# theremin.net
KiCad netlist of a schematic drawn in Altium Designer
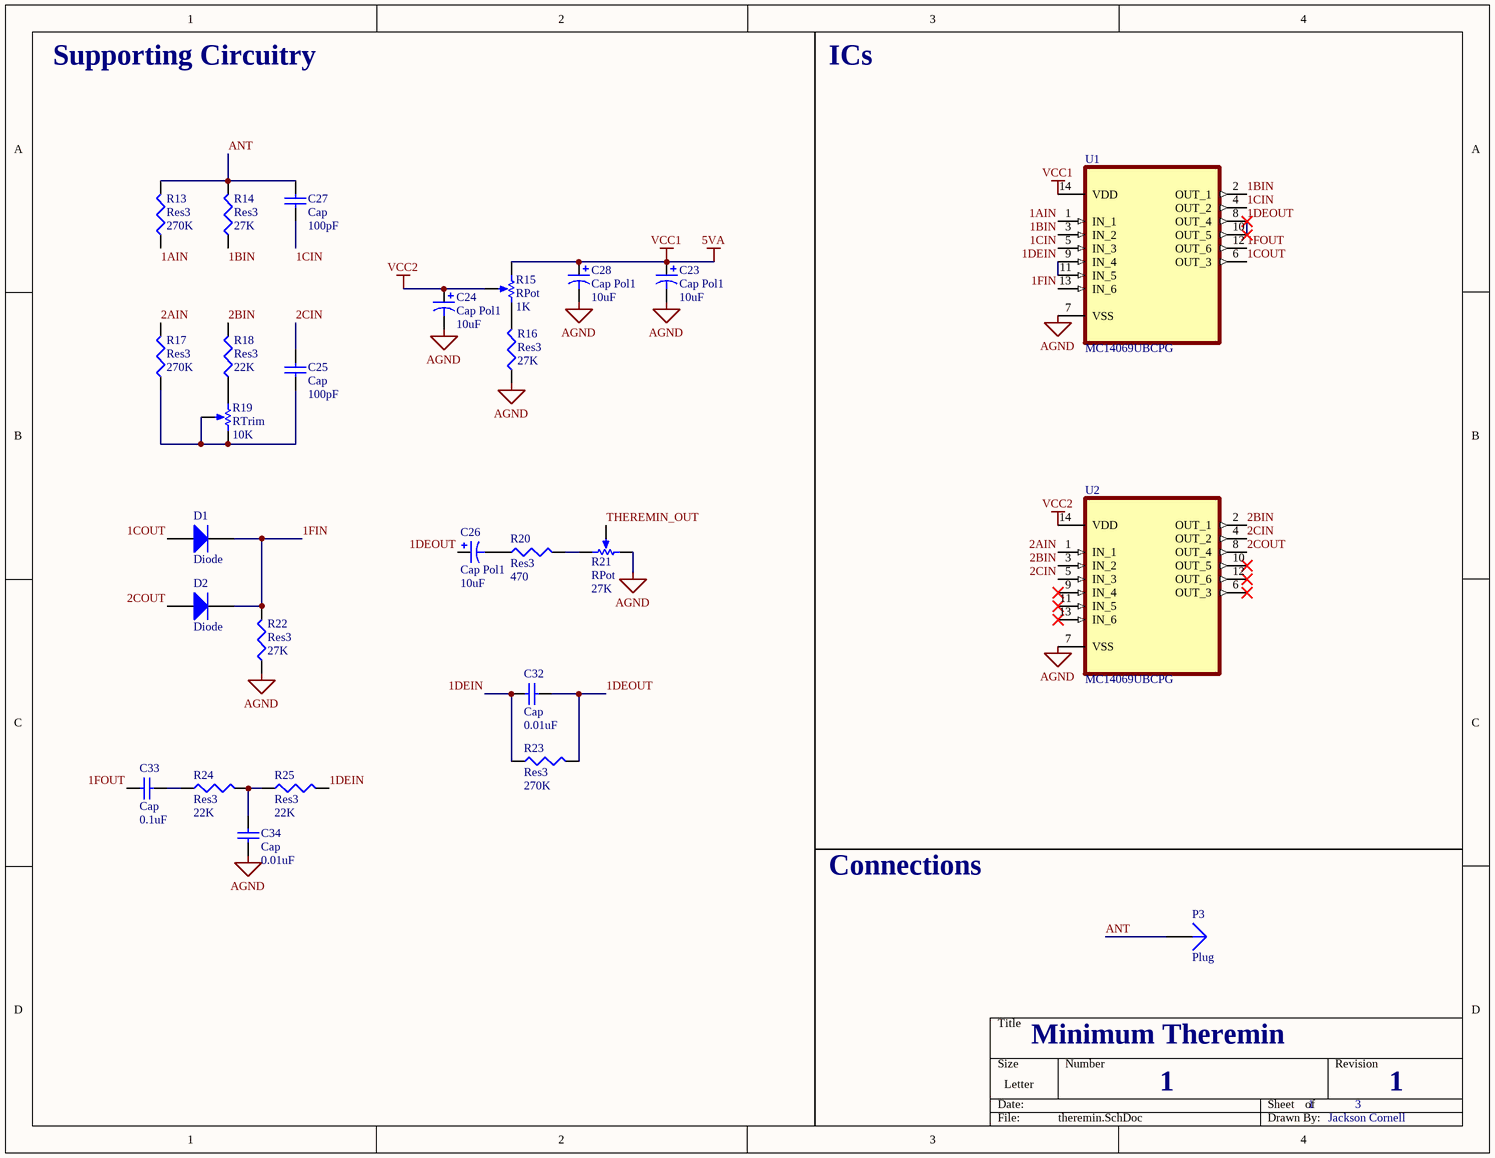
[diagram p0: theremin.SchDoc]

(export (version "E")
  (design (tool "Eeschema 10.0.6"))
  (components
    (comp (ref "C23")
      (value "Cap Pol1")
      (footprint "Passives:CAPC0805")
      (description "Polarized Capacitor (Radial)")
      (fields (field (name "ALTIUM_VALUE") "10uF") (field (name "PUBLISHER") "Altium Limited"))
      (libsource (lib "Miscellaneous Devices") (part "Cap Pol1"))
    )
    (comp (ref "C24")
      (value "Cap Pol1")
      (footprint "Passives:CAPC0805")
      (description "Polarized Capacitor (Radial)")
      (fields (field (name "ALTIUM_VALUE") "10uF") (field (name "PUBLISHER") "Altium Limited"))
      (libsource (lib "Miscellaneous Devices") (part "Cap Pol1"))
    )
    (comp (ref "C25")
      (value "Cap")
      (footprint "Passives:CAPC0805")
      (description "Capacitor")
      (fields (field (name "ALTIUM_VALUE") "100pF") (field (name "PUBLISHER") "Altium Limited"))
      (libsource (lib "Miscellaneous Devices") (part "Cap"))
    )
    (comp (ref "C26")
      (value "Cap Pol1")
      (footprint "Passives:CAPC0805")
      (description "Polarized Capacitor (Radial)")
      (fields (field (name "ALTIUM_VALUE") "10uF") (field (name "PUBLISHER") "Altium Limited"))
      (libsource (lib "Miscellaneous Devices") (part "Cap Pol1"))
    )
    (comp (ref "C27")
      (value "Cap")
      (footprint "Passives:CAPC0805")
      (description "Capacitor")
      (fields (field (name "ALTIUM_VALUE") "100pF") (field (name "PUBLISHER") "Altium Limited"))
      (libsource (lib "Miscellaneous Devices") (part "Cap"))
    )
    (comp (ref "C28")
      (value "Cap Pol1")
      (footprint "Passives:CAPC0805")
      (description "Polarized Capacitor (Radial)")
      (fields (field (name "ALTIUM_VALUE") "10uF") (field (name "PUBLISHER") "Altium Limited"))
      (libsource (lib "Miscellaneous Devices") (part "Cap Pol1"))
    )
    (comp (ref "C32")
      (value "Cap")
      (footprint "Passives:CAPC0805")
      (description "Capacitor")
      (fields (field (name "ALTIUM_VALUE") "0.01uF") (field (name "PUBLISHER") "Altium Limited"))
      (libsource (lib "Miscellaneous Devices") (part "Cap"))
    )
    (comp (ref "C33")
      (value "Cap")
      (footprint "Passives:CAPC0805")
      (description "Capacitor")
      (fields (field (name "ALTIUM_VALUE") "0.1uF") (field (name "PUBLISHER") "Altium Limited"))
      (libsource (lib "Miscellaneous Devices") (part "Cap"))
    )
    (comp (ref "C34")
      (value "Cap")
      (footprint "Passives:CAPC0805")
      (description "Capacitor")
      (fields (field (name "ALTIUM_VALUE") "0.01uF") (field (name "PUBLISHER") "Altium Limited"))
      (libsource (lib "Miscellaneous Devices") (part "Cap"))
    )
    (comp (ref "D1")
      (value "Diode")
      (footprint "SMC")
      (description "Default Diode")
      (fields (field (name "PUBLISHER") "Altium Limited"))
      (libsource (lib "Miscellaneous Devices") (part "Diode"))
    )
    (comp (ref "D2")
      (value "Diode")
      (footprint "SMC")
      (description "Default Diode")
      (fields (field (name "PUBLISHER") "Altium Limited"))
      (libsource (lib "Miscellaneous Devices") (part "Diode"))
    )
    (comp (ref "P3")
      (value "Plug")
      (footprint "PIN1")
      (fields (field (name "PUBLISHER") "Altium Limited"))
      (libsource (lib "Miscellaneous Connectors") (part "Plug"))
    )
    (comp (ref "R13")
      (value "Res3")
      (footprint "Passives:RES0805")
      (description "Resistor")
      (fields (field (name "ALTIUM_VALUE") "270K") (field (name "PUBLISHER") "Altium Limited"))
      (libsource (lib "Miscellaneous Devices") (part "Res3"))
    )
    (comp (ref "R14")
      (value "Res3")
      (footprint "Passives:RES0805")
      (description "Resistor")
      (fields (field (name "ALTIUM_VALUE") "27K") (field (name "PUBLISHER") "Altium Limited"))
      (libsource (lib "Miscellaneous Devices") (part "Res3"))
    )
    (comp (ref "R15")
      (value "RPot")
      (footprint "HDR1X3")
      (description "Potentiometer")
      (fields (field (name "ALTIUM_VALUE") "1K") (field (name "PUBLISHER") "Altium Limited"))
      (libsource (lib "Miscellaneous Devices") (part "RPot"))
    )
    (comp (ref "R16")
      (value "Res3")
      (footprint "Passives:RES0805")
      (description "Resistor")
      (fields (field (name "ALTIUM_VALUE") "27K") (field (name "PUBLISHER") "Altium Limited"))
      (libsource (lib "Miscellaneous Devices") (part "Res3"))
    )
    (comp (ref "R17")
      (value "Res3")
      (footprint "Passives:RES0805")
      (description "Resistor")
      (fields (field (name "ALTIUM_VALUE") "270K") (field (name "PUBLISHER") "Altium Limited"))
      (libsource (lib "Miscellaneous Devices") (part "Res3"))
    )
    (comp (ref "R18")
      (value "Res3")
      (footprint "Passives:RES0805")
      (description "Resistor")
      (fields (field (name "ALTIUM_VALUE") "22K") (field (name "PUBLISHER") "Altium Limited"))
      (libsource (lib "Miscellaneous Devices") (part "Res3"))
    )
    (comp (ref "R19")
      (value "RTrim")
      (footprint "VR5")
      (description "Potentiometer")
      (fields (field (name "ALTIUM_VALUE") "10K") (field (name "PUBLISHER") "Altium Limited"))
      (libsource (lib "Miscellaneous Devices") (part "RPot"))
    )
    (comp (ref "R20")
      (value "Res3")
      (footprint "Passives:RES0805")
      (description "Resistor")
      (fields (field (name "ALTIUM_VALUE") "470") (field (name "PUBLISHER") "Altium Limited"))
      (libsource (lib "Miscellaneous Devices") (part "Res3"))
    )
    (comp (ref "R21")
      (value "RPot")
      (footprint "HDR1X3")
      (description "Potentiometer")
      (fields (field (name "ALTIUM_VALUE") "27K") (field (name "PUBLISHER") "Altium Limited"))
      (libsource (lib "Miscellaneous Devices") (part "RPot"))
    )
    (comp (ref "R22")
      (value "Res3")
      (footprint "Passives:RES0805")
      (description "Resistor")
      (fields (field (name "ALTIUM_VALUE") "27K") (field (name "PUBLISHER") "Altium Limited"))
      (libsource (lib "Miscellaneous Devices") (part "Res3"))
    )
    (comp (ref "R23")
      (value "Res3")
      (footprint "Passives:RES0805")
      (description "Resistor")
      (fields (field (name "ALTIUM_VALUE") "270K") (field (name "PUBLISHER") "Altium Limited"))
      (libsource (lib "Miscellaneous Devices") (part "Res3"))
    )
    (comp (ref "R24")
      (value "Res3")
      (footprint "Passives:RES0805")
      (description "Resistor")
      (fields (field (name "ALTIUM_VALUE") "22K") (field (name "PUBLISHER") "Altium Limited"))
      (libsource (lib "Miscellaneous Devices") (part "Res3"))
    )
    (comp (ref "R25")
      (value "Res3")
      (footprint "Passives:RES0805")
      (description "Resistor")
      (fields (field (name "ALTIUM_VALUE") "22K") (field (name "PUBLISHER") "Altium Limited"))
      (libsource (lib "Miscellaneous Devices") (part "Res3"))
    )
    (comp (ref "U1")
      (value "MC14069UBCPG")
      (footprint "DIP254P762X469-14")
      (description "Inverter IC 6 Channel - 14-PDIP")
      (fields (field (name "MF") "ON Semiconductor"))
      (libsource (lib "MC14069UBCPG") (part "MC14069UBCPG"))
    )
    (comp (ref "U2")
      (value "MC14069UBCPG")
      (footprint "DIP254P762X469-14")
      (description "Inverter IC 6 Channel - 14-PDIP")
      (fields (field (name "MF") "ON Semiconductor"))
      (libsource (lib "MC14069UBCPG") (part "MC14069UBCPG"))
    )
  )
  (nets
    (net (code "1") (name "/1AIN") (class "Default")
      (node (ref "R13") (pin "1") (pinfunction "1_1") (pintype "passive"))
      (node (ref "U1") (pin "1") (pinfunction "IN_1_1") (pintype "input"))
    )
    (net (code "2") (name "/1BIN") (class "Default")
      (node (ref "R14") (pin "1") (pinfunction "1_1") (pintype "passive"))
      (node (ref "U1") (pin "2") (pinfunction "OUT_1_2") (pintype "output"))
      (node (ref "U1") (pin "3") (pinfunction "IN_2_3") (pintype "input"))
    )
    (net (code "3") (name "/1CIN") (class "Default")
      (node (ref "C27") (pin "1") (pinfunction "1_1") (pintype "passive"))
      (node (ref "U1") (pin "4") (pinfunction "OUT_2_4") (pintype "output"))
      (node (ref "U1") (pin "5") (pinfunction "IN_3_5") (pintype "input"))
    )
    (net (code "4") (name "/1COUT") (class "Default")
      (node (ref "D1") (pin "1") (pinfunction "A_1") (pintype "passive"))
      (node (ref "U1") (pin "6") (pinfunction "OUT_3_6") (pintype "output"))
    )
    (net (code "5") (name "/1DEIN") (class "Default")
      (node (ref "C32") (pin "1") (pinfunction "1_1") (pintype "passive"))
      (node (ref "R23") (pin "1") (pinfunction "1_1") (pintype "passive"))
      (node (ref "R25") (pin "2") (pinfunction "2_2") (pintype "passive"))
      (node (ref "U1") (pin "11") (pinfunction "IN_5_11") (pintype "input"))
      (node (ref "U1") (pin "9") (pinfunction "IN_4_9") (pintype "input"))
    )
    (net (code "6") (name "/1DEOUT") (class "Default")
      (node (ref "C26") (pin "1") (pinfunction "1_1") (pintype "passive"))
      (node (ref "C32") (pin "2") (pinfunction "2_2") (pintype "passive"))
      (node (ref "R23") (pin "2") (pinfunction "2_2") (pintype "passive"))
      (node (ref "U1") (pin "10") (pinfunction "OUT_5_10") (pintype "output"))
      (node (ref "U1") (pin "8") (pinfunction "OUT_4_8") (pintype "output"))
    )
    (net (code "7") (name "/1FIN") (class "Default")
      (node (ref "D1") (pin "2") (pinfunction "K_2") (pintype "passive"))
      (node (ref "D2") (pin "2") (pinfunction "K_2") (pintype "passive"))
      (node (ref "R22") (pin "2") (pinfunction "2_2") (pintype "passive"))
      (node (ref "U1") (pin "13") (pinfunction "IN_6_13") (pintype "input"))
    )
    (net (code "8") (name "/1FOUT") (class "Default")
      (node (ref "C33") (pin "1") (pinfunction "1_1") (pintype "passive"))
      (node (ref "U1") (pin "12") (pinfunction "OUT_6_12") (pintype "output"))
    )
    (net (code "9") (name "/2AIN") (class "Default")
      (node (ref "R17") (pin "2") (pinfunction "2_2") (pintype "passive"))
      (node (ref "U2") (pin "1") (pinfunction "IN_1_1") (pintype "input"))
    )
    (net (code "10") (name "/2BIN") (class "Default")
      (node (ref "R18") (pin "2") (pinfunction "2_2") (pintype "passive"))
      (node (ref "U2") (pin "2") (pinfunction "OUT_1_2") (pintype "output"))
      (node (ref "U2") (pin "3") (pinfunction "IN_2_3") (pintype "input"))
    )
    (net (code "11") (name "/2CIN") (class "Default")
      (node (ref "C25") (pin "2") (pinfunction "2_2") (pintype "passive"))
      (node (ref "U2") (pin "4") (pinfunction "OUT_2_4") (pintype "output"))
      (node (ref "U2") (pin "5") (pinfunction "IN_3_5") (pintype "input"))
    )
    (net (code "12") (name "/2COUT") (class "Default")
      (node (ref "D2") (pin "1") (pinfunction "A_1") (pintype "passive"))
      (node (ref "U2") (pin "8") (pinfunction "OUT_4_8") (pintype "output"))
    )
    (net (code "13") (name "/ANT") (class "Default")
      (node (ref "C27") (pin "2") (pinfunction "2_2") (pintype "passive"))
      (node (ref "P3") (pin "1") (pinfunction "1_1") (pintype "passive"))
      (node (ref "R13") (pin "2") (pinfunction "2_2") (pintype "passive"))
      (node (ref "R14") (pin "2") (pinfunction "2_2") (pintype "passive"))
    )
    (net (code "14") (name "/THEREMIN_OUT") (class "Default")
      (node (ref "R21") (pin "3") (pinfunction "TAP_3") (pintype "passive"))
    )
    (net (code "15") (name "5VA") (class "Default")
      (node (ref "C23") (pin "1") (pinfunction "1_1") (pintype "passive"))
      (node (ref "C28") (pin "1") (pinfunction "1_1") (pintype "passive"))
      (node (ref "R15") (pin "1") (pinfunction "TOP_1") (pintype "passive"))
      (node (ref "U1") (pin "14") (pinfunction "VDD_14") (pintype "power_in"))
    )
    (net (code "16") (name "AGND") (class "Default")
      (node (ref "C23") (pin "2") (pinfunction "2_2") (pintype "passive"))
      (node (ref "C24") (pin "2") (pinfunction "2_2") (pintype "passive"))
      (node (ref "C28") (pin "2") (pinfunction "2_2") (pintype "passive"))
      (node (ref "C34") (pin "1") (pinfunction "1_1") (pintype "passive"))
      (node (ref "R16") (pin "1") (pinfunction "1_1") (pintype "passive"))
      (node (ref "R21") (pin "1") (pinfunction "TOP_1") (pintype "passive"))
      (node (ref "R22") (pin "1") (pinfunction "1_1") (pintype "passive"))
      (node (ref "U1") (pin "7") (pinfunction "VSS_7") (pintype "power_in"))
      (node (ref "U2") (pin "7") (pinfunction "VSS_7") (pintype "power_in"))
    )
    (net (code "17") (name "Net-(C26-Pad2)") (class "Default")
      (node (ref "C26") (pin "2") (pinfunction "2_2") (pintype "passive"))
      (node (ref "R20") (pin "1") (pinfunction "1_1") (pintype "passive"))
    )
    (net (code "18") (name "Net-(C33-Pad2)") (class "Default")
      (node (ref "C33") (pin "2") (pinfunction "2_2") (pintype "passive"))
      (node (ref "R24") (pin "1") (pinfunction "1_1") (pintype "passive"))
    )
    (net (code "19") (name "Net-(C34-Pad2)") (class "Default")
      (node (ref "C34") (pin "2") (pinfunction "2_2") (pintype "passive"))
      (node (ref "R24") (pin "2") (pinfunction "2_2") (pintype "passive"))
      (node (ref "R25") (pin "1") (pinfunction "1_1") (pintype "passive"))
    )
    (net (code "20") (name "Net-(R15-BOT)") (class "Default")
      (node (ref "R15") (pin "2") (pinfunction "BOT_2") (pintype "passive"))
      (node (ref "R16") (pin "2") (pinfunction "2_2") (pintype "passive"))
    )
    (net (code "21") (name "Net-(R19-BOT)") (class "Default")
      (node (ref "C25") (pin "1") (pinfunction "1_1") (pintype "passive"))
      (node (ref "R17") (pin "1") (pinfunction "1_1") (pintype "passive"))
      (node (ref "R19") (pin "2") (pinfunction "BOT_2") (pintype "passive"))
      (node (ref "R19") (pin "3") (pinfunction "TAP_3") (pintype "passive"))
    )
    (net (code "22") (name "Net-(R19-TOP)") (class "Default")
      (node (ref "R18") (pin "1") (pinfunction "1_1") (pintype "passive"))
      (node (ref "R19") (pin "1") (pinfunction "TOP_1") (pintype "passive"))
    )
    (net (code "23") (name "Net-(R21-BOT)") (class "Default")
      (node (ref "R20") (pin "2") (pinfunction "2_2") (pintype "passive"))
      (node (ref "R21") (pin "2") (pinfunction "BOT_2") (pintype "passive"))
    )
    (net (code "24") (name "VCC2") (class "Default")
      (node (ref "C24") (pin "1") (pinfunction "1_1") (pintype "passive"))
      (node (ref "R15") (pin "3") (pinfunction "TAP_3") (pintype "passive"))
      (node (ref "U2") (pin "14") (pinfunction "VDD_14") (pintype "power_in"))
    )
    (net (code "25") (name "unconnected-(U2-IN_4-Pad9)") (class "Default")
      (node (ref "U2") (pin "9") (pinfunction "IN_4_9") (pintype "input+no_connect"))
    )
    (net (code "26") (name "unconnected-(U2-IN_5-Pad11)") (class "Default")
      (node (ref "U2") (pin "11") (pinfunction "IN_5_11") (pintype "input+no_connect"))
    )
    (net (code "27") (name "unconnected-(U2-IN_6-Pad13)") (class "Default")
      (node (ref "U2") (pin "13") (pinfunction "IN_6_13") (pintype "input+no_connect"))
    )
    (net (code "28") (name "unconnected-(U2-OUT_3-Pad6)") (class "Default")
      (node (ref "U2") (pin "6") (pinfunction "OUT_3_6") (pintype "output+no_connect"))
    )
    (net (code "29") (name "unconnected-(U2-OUT_5-Pad10)") (class "Default")
      (node (ref "U2") (pin "10") (pinfunction "OUT_5_10") (pintype "output+no_connect"))
    )
    (net (code "30") (name "unconnected-(U2-OUT_6-Pad12)") (class "Default")
      (node (ref "U2") (pin "12") (pinfunction "OUT_6_12") (pintype "output+no_connect"))
    )
  )
)
